# RF_Antenna_Power.net
KiCad netlist of a schematic drawn in Altium Designer
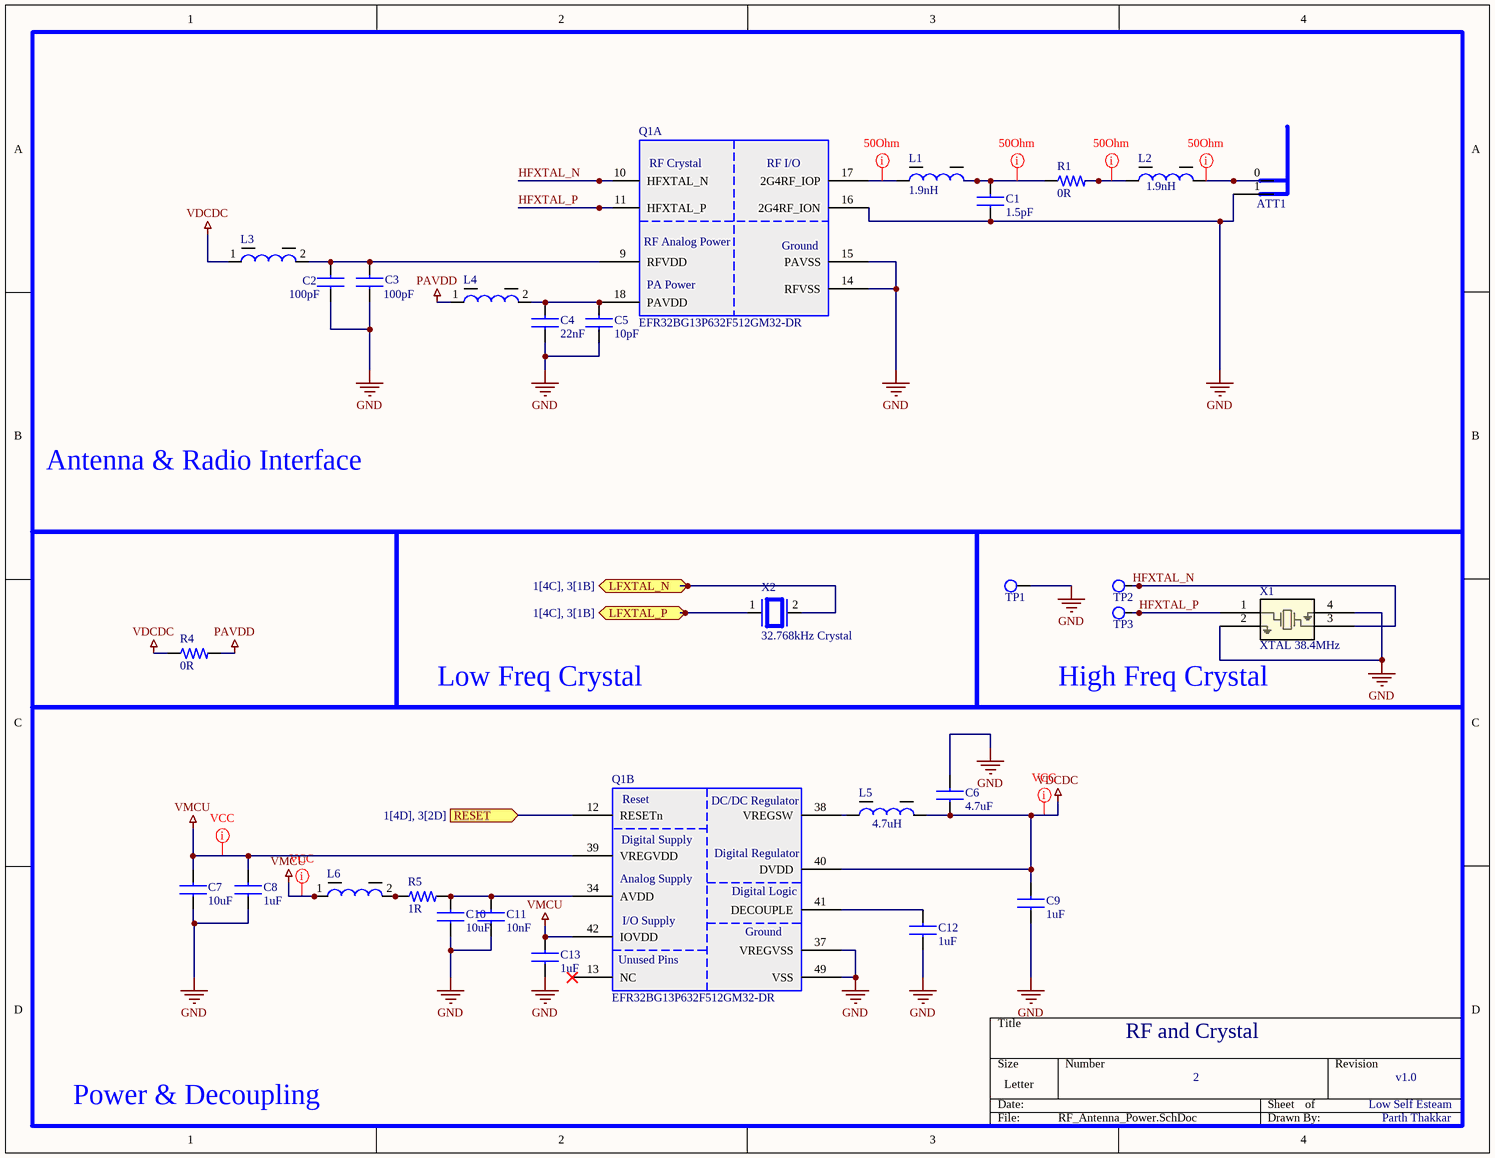
[diagram p0: RF_Antenna_Power.SchDoc]

(export (version "E")
  (design (tool "Eeschema 10.0.6"))
  (components
    (comp (ref "ATT1")
      (value "F_Interverted")
      (footprint "F_Inverted")
      (description "For 50Ohm impedence, Inverted F antenna")
      (libsource (lib "Keyboard_parts") (part "F_Interverted"))
    )
    (comp (ref "C1")
      (value "1.5pF")
      (footprint "Capacitor 0402")
      (fields
        (field (name "MANUFACTURER") "Murata")
        (field (name "MANUFACTURER PART NUMBER") "GJM1555C1H1R5WB01D")
        (field (name "Comment") "CAP 1.5pF 50V 0402")
      )
      (libsource (lib "Keyboard_parts") (part "CAP 1.5pF 50V 0402"))
    )
    (comp (ref "C2")
      (value "100pF")
      (footprint "Capacitor 0603")
      (fields
        (field (name "MANUFACTURER") "Murata")
        (field (name "MANUFACTURER PART NUMBER") "GCM1885C2A101JA16D")
        (field (name "Comment") "CAP 100pF 100V 0603")
      )
      (libsource (lib "Keyboard_parts") (part "CAP 100pF 100V 0603"))
    )
    (comp (ref "C3")
      (value "100pF")
      (footprint "Capacitor 0603")
      (fields
        (field (name "MANUFACTURER") "Murata")
        (field (name "MANUFACTURER PART NUMBER") "GCM1885C2A101JA16D")
        (field (name "Comment") "CAP 100pF 100V 0603")
      )
      (libsource (lib "Keyboard_parts") (part "CAP 100pF 100V 0603"))
    )
    (comp (ref "C4")
      (value "22nF")
      (footprint "Capacitor 0603")
      (fields
        (field (name "MANUFACTURER") "Murata")
        (field (name "MANUFACTURER PART NUMBER") "GRM155R71H223KA12D")
        (field (name "Comment") "CAP 220nF 50V 0603")
      )
      (libsource (lib "Keyboard_parts") (part "CAP 220nF 50V 0603"))
    )
    (comp (ref "C5")
      (value "10pF")
      (footprint "Capacitor 0603")
      (fields
        (field (name "MANUFACTURER") "Murata")
        (field (name "MANUFACTURER PART NUMBER") "GRM1555C1H100FA01D")
        (field (name "Comment") "CAP 10pF 50V 0603")
      )
      (libsource (lib "Keyboard_parts") (part "CAP 10pF 50V 0603"))
    )
    (comp (ref "C6")
      (value "4.7uF")
      (footprint "Capacitor 0603")
      (fields
        (field (name "MANUFACTURER") "Murata")
        (field (name "MANUFACTURER PART NUMBER") "GRT188R61E475KE13D")
        (field (name "Comment") "CAP 4.7uF 25V 0603")
      )
      (libsource (lib "Keyboard_parts") (part "CAP 4.7uF 25V 0603"))
    )
    (comp (ref "C7")
      (value "10uF")
      (footprint "Capacitor 0603")
      (fields
        (field (name "MANUFACTURER") "Murata")
        (field (name "MANUFACTURER PART NUMBER") "GRM188R61A106ME69D")
        (field (name "Comment") "CAP 10uF 10V 0603")
      )
      (libsource (lib "Keyboard_parts") (part "CAP 10uF 10V 0603"))
    )
    (comp (ref "C8")
      (value "1uF")
      (footprint "Capacitor 0603")
      (fields
        (field (name "MANUFACTURER") "Murata")
        (field (name "MANUFACTURER PART NUMBER") "GRM188R61A105KA61D")
        (field (name "Comment") "CAP 1uF 10V 0603")
      )
      (libsource (lib "Keyboard_parts") (part "CAP 1uF 10V 0603"))
    )
    (comp (ref "C9")
      (value "1uF")
      (footprint "Capacitor 0603")
      (fields
        (field (name "MANUFACTURER") "Murata")
        (field (name "MANUFACTURER PART NUMBER") "GRM188R61A105KA61D")
        (field (name "Comment") "CAP 1uF 10V 0603")
      )
      (libsource (lib "Keyboard_parts") (part "CAP 1uF 10V 0603"))
    )
    (comp (ref "C10")
      (value "10uF")
      (footprint "Capacitor 0603")
      (fields
        (field (name "MANUFACTURER") "Murata")
        (field (name "MANUFACTURER PART NUMBER") "GRM188R61A106ME69D")
        (field (name "Comment") "CAP 10uF 10V 0603")
      )
      (libsource (lib "Keyboard_parts") (part "CAP 10uF 10V 0603"))
    )
    (comp (ref "C11")
      (value "10nF")
      (footprint "Capacitor 0603")
      (fields
        (field (name "MANUFACTURER") "Murata")
        (field (name "MANUFACTURER PART NUMBER") "GCM188R72A103KA37D")
        (field (name "Comment") "CAP 10nF 100V 0603")
      )
      (libsource (lib "Keyboard_parts") (part "CAP 10nF 100V 0603"))
    )
    (comp (ref "C12")
      (value "1uF")
      (footprint "Capacitor 0603")
      (fields
        (field (name "MANUFACTURER") "Murata")
        (field (name "MANUFACTURER PART NUMBER") "GRM188R61A105KA61D")
        (field (name "Comment") "CAP 1uF 10V 0603")
      )
      (libsource (lib "Keyboard_parts") (part "CAP 1uF 10V 0603"))
    )
    (comp (ref "C13")
      (value "1uF")
      (footprint "Capacitor 0603")
      (fields
        (field (name "MANUFACTURER") "Murata")
        (field (name "MANUFACTURER PART NUMBER") "GRM188R61A105KA61D")
        (field (name "Comment") "CAP 1uF 10V 0603")
      )
      (libsource (lib "Keyboard_parts") (part "CAP 1uF 10V 0603"))
    )
    (comp (ref "L1")
      (value "1.9nH")
      (footprint "Ferrite 0402")
      (description "Inductor Chip 1.9nH 0.3nH Tolerance 2-Pin 0402 Paper T/R")
      (fields
        (field (name "MANUFACTURER") "Murata")
        (field (name "MANUFACTURER PART NUMBER") "LQG15WZ1N9S02D")
      )
      (libsource (lib "Keyboard_parts") (part "IND 1.9nH 0402"))
    )
    (comp (ref "L2")
      (value "1.9nH")
      (footprint "Ferrite 0402")
      (description "Inductor Chip 1.9nH 0.3nH Tolerance 2-Pin 0402 Paper T/R")
      (fields
        (field (name "MANUFACTURER") "Murata")
        (field (name "MANUFACTURER PART NUMBER") "LQG15WZ1N9S02D")
      )
      (libsource (lib "Keyboard_parts") (part "IND 1.9nH 0402"))
    )
    (comp (ref "L3")
      (value "Ferrite Bead 600(601) 1LN")
      (footprint "Ferrite 0603")
      (description "RFVDD, PAVDD, EFR")
      (fields
        (field (name "MANUFACTURER") "Murata")
        (field (name "MANUFACTURER PART NUMBER") "BLM18AG601SN1D")
      )
      (libsource (lib "Keyboard_parts") (part "Ferrite Bead 600(601) 1LN"))
    )
    (comp (ref "L4")
      (value "Ferrite Bead 600(601) 1LN")
      (footprint "Ferrite 0603")
      (description "RFVDD, PAVDD, EFR")
      (fields
        (field (name "MANUFACTURER") "Murata")
        (field (name "MANUFACTURER PART NUMBER") "BLM18AG601SN1D")
      )
      (libsource (lib "Keyboard_parts") (part "Ferrite Bead 600(601) 1LN"))
    )
    (comp (ref "L5")
      (value "IND 4.7uH 1515")
      (footprint "IND 22uH (1.6x4.3)")
      (description "General Purpose Inductor, 4.7uH, 30%, 1 Element, Ferrite-Core, SMD, 1515")
      (fields
        (field (name "MANUFACTURER") "Wurth Electronics")
        (field (name "MANUFACTURER PART NUMBER") "744031004")
        (field (name "INDUCTANCE-NOM (L)") "4.7uH")
      )
      (libsource (lib "Keyboard_parts") (part "IND 4.7uH 1515"))
    )
    (comp (ref "L6")
      (value "Farrite Bead 102(1k)")
      (footprint "Ferrite 0402")
      (description "Ferrite Chip, 1 Function(s), 0.05A, 2 Pin(s)")
      (fields
        (field (name "MANUFACTURER") "Wurth Electronics")
        (field (name "MANUFACTURER PART NUMBER") "742841210")
      )
      (libsource (lib "Keyboard_parts") (part "Farrite Bead 102(1k)"))
    )
    (comp (ref "Q1")
      (value "EFR32BG13P632F512GM32-DR")
      (footprint "EFR32BG")
      (description "BLue Gecko")
      (fields (field (name "MANUFACTURER") "Silicon Labs"))
      (libsource (lib "Keyboard_parts") (part "EFR32BG13P632F512GM32-DR"))
    )
    (comp (ref "R1")
      (value "0R")
      (footprint "Resistor 0402")
      (description "Metal Glaze/thick Film, 0.0625W, 0ohm, Surface Mount, 0402")
      (fields
        (field (name "MANUFACTURER") "Yageo")
        (field (name "MANUFACTURER PART NUMBER") "RC0402JR-070RL")
      )
      (libsource (lib "Keyboard_parts") (part "RES 0R 0402"))
    )
    (comp (ref "R4")
      (value "0R")
      (footprint "Resistor 0402")
      (description "Metal Glaze/thick Film, 0.0625W, 0ohm, Surface Mount, 0402")
      (fields
        (field (name "MANUFACTURER") "Yageo")
        (field (name "MANUFACTURER PART NUMBER") "RC0402JR-070RL")
      )
      (libsource (lib "Keyboard_parts") (part "RES 0R 0402"))
    )
    (comp (ref "R5")
      (value "1R")
      (footprint "Resistor 0603")
      (fields
        (field (name "MANUFACTURER") "Yageo")
        (field (name "MANUFACTURER PART NUMBER") "RC0603FR-071RL")
        (field (name "TOLERANCE") "1%")
      )
      (libsource (lib "Keyboard_parts") (part "RES 1R 0603"))
    )
    (comp (ref "TP1")
      (value "Test point")
      (footprint "Test Point")
      (libsource (lib "Keyboard_parts") (part "Test point"))
    )
    (comp (ref "TP2")
      (value "Test point")
      (footprint "Test Point")
      (libsource (lib "Keyboard_parts") (part "Test point"))
    )
    (comp (ref "TP3")
      (value "Test point")
      (footprint "Test Point")
      (libsource (lib "Keyboard_parts") (part "Test point"))
    )
    (comp (ref "X1")
      (value "XTAL 38.4MHz")
      (footprint "XTAL 38.4MHz")
      (description "Crystal 38.4000MHZ 10PF SMD")
      (fields
        (field (name "MANUFACTURER") "Murata")
        (field (name "MANUFACTURER PART NUMBER") "XRCGB38M400F1S3JR0")
      )
      (libsource (lib "Keyboard_parts") (part "XTAL 38.4MHz"))
    )
    (comp (ref "X2")
      (value "32.768kHz Crystal")
      (footprint "XTAL_32.768KHZ-T")
      (description "Crystal 0.032768MHz ±20ppm (Tol) 12.5pF Flexural 70000Ohm 2-Pin CSMD T/R")
      (fields
        (field (name "MANUFACTURER") "Abracon")
        (field (name "MANUFACTURER PART NUMBER") "ABS07-32.768KHZ-H-T")
      )
      (libsource (lib "Keyboard_parts") (part "32.768kHz Crystal"))
    )
  )
  (nets
    (net (code "1") (name "/HFXTAL_N") (class "Default")
      (node (ref "Q1") (pin "10") (pinfunction "HFXTAL_N_10") (pintype "passive"))
      (node (ref "TP2") (pin "1") (pinfunction "1_1") (pintype "passive"))
      (node (ref "X1") (pin "3") (pinfunction "3_3") (pintype "passive"))
    )
    (net (code "2") (name "/HFXTAL_P") (class "Default")
      (node (ref "Q1") (pin "11") (pinfunction "HFXTAL_P_11") (pintype "passive"))
      (node (ref "TP3") (pin "1") (pinfunction "1_1") (pintype "passive"))
      (node (ref "X1") (pin "1") (pinfunction "1_1") (pintype "passive"))
    )
    (net (code "3") (name "/LFXTAL_N") (class "Default")
      (node (ref "X2") (pin "2") (pinfunction "2_2") (pintype "passive"))
    )
    (net (code "4") (name "/LFXTAL_P") (class "Default")
      (node (ref "X2") (pin "1") (pinfunction "1_1") (pintype "passive"))
    )
    (net (code "5") (name "/RESET") (class "Default")
      (node (ref "Q1") (pin "12") (pinfunction "RESETn_12") (pintype "passive"))
    )
    (net (code "6") (name "GND") (class "Default")
      (node (ref "ATT1") (pin "1") (pinfunction "GND_1") (pintype "passive"))
      (node (ref "C1") (pin "2") (pinfunction "2_2") (pintype "passive"))
      (node (ref "C10") (pin "2") (pinfunction "2_2") (pintype "passive"))
      (node (ref "C11") (pin "2") (pinfunction "2_2") (pintype "passive"))
      (node (ref "C12") (pin "2") (pinfunction "2_2") (pintype "passive"))
      (node (ref "C13") (pin "2") (pinfunction "2_2") (pintype "passive"))
      (node (ref "C2") (pin "2") (pinfunction "2_2") (pintype "passive"))
      (node (ref "C3") (pin "2") (pinfunction "2_2") (pintype "passive"))
      (node (ref "C4") (pin "2") (pinfunction "2_2") (pintype "passive"))
      (node (ref "C5") (pin "2") (pinfunction "2_2") (pintype "passive"))
      (node (ref "C6") (pin "2") (pinfunction "2_2") (pintype "passive"))
      (node (ref "C7") (pin "2") (pinfunction "2_2") (pintype "passive"))
      (node (ref "C8") (pin "2") (pinfunction "2_2") (pintype "passive"))
      (node (ref "C9") (pin "2") (pinfunction "2_2") (pintype "passive"))
      (node (ref "Q1") (pin "14") (pinfunction "RFVSS_14") (pintype "power_in"))
      (node (ref "Q1") (pin "15") (pinfunction "PAVSS_15") (pintype "power_in"))
      (node (ref "Q1") (pin "16") (pinfunction "2G4RF_ION_16") (pintype "passive"))
      (node (ref "Q1") (pin "37") (pinfunction "VREGVSS_37") (pintype "power_in"))
      (node (ref "Q1") (pin "49") (pinfunction "VSS_49") (pintype "power_in"))
      (node (ref "TP1") (pin "1") (pinfunction "1_1") (pintype "passive"))
      (node (ref "X1") (pin "2") (pinfunction "2_2") (pintype "passive"))
      (node (ref "X1") (pin "4") (pinfunction "4_4") (pintype "passive"))
    )
    (net (code "7") (name "Net-(ATT1-FEED)") (class "Default")
      (node (ref "ATT1") (pin "0") (pinfunction "FEED_0") (pintype "passive"))
      (node (ref "L2") (pin "2") (pinfunction "2_2") (pintype "passive"))
    )
    (net (code "8") (name "Net-(C1-Pad1)") (class "Default")
      (node (ref "C1") (pin "1") (pinfunction "1_1") (pintype "passive"))
      (node (ref "L1") (pin "2") (pinfunction "2_2") (pintype "passive"))
      (node (ref "R1") (pin "1") (pinfunction "1_1") (pintype "passive"))
    )
    (net (code "9") (name "Net-(L2-Pad1)") (class "Default")
      (node (ref "L2") (pin "1") (pinfunction "1_1") (pintype "passive"))
      (node (ref "R1") (pin "2") (pinfunction "2_2") (pintype "passive"))
    )
    (net (code "10") (name "Net-(L6-Pad2)") (class "Default")
      (node (ref "L6") (pin "2") (pinfunction "2_2") (pintype "passive"))
      (node (ref "R5") (pin "1") (pinfunction "1_1") (pintype "passive"))
    )
    (net (code "11") (name "Net-(Q1A-2G4RF_IOP)") (class "Default")
      (node (ref "L1") (pin "1") (pinfunction "1_1") (pintype "passive"))
      (node (ref "Q1") (pin "17") (pinfunction "2G4RF_IOP_17") (pintype "passive"))
    )
    (net (code "12") (name "Net-(Q1A-PAVDD)") (class "Default")
      (node (ref "C4") (pin "1") (pinfunction "1_1") (pintype "passive"))
      (node (ref "C5") (pin "1") (pinfunction "1_1") (pintype "passive"))
      (node (ref "L4") (pin "2") (pinfunction "2_2") (pintype "passive"))
      (node (ref "Q1") (pin "18") (pinfunction "PAVDD_18") (pintype "power_in"))
    )
    (net (code "13") (name "Net-(Q1A-RFVDD)") (class "Default")
      (node (ref "C2") (pin "1") (pinfunction "1_1") (pintype "passive"))
      (node (ref "C3") (pin "1") (pinfunction "1_1") (pintype "passive"))
      (node (ref "L3") (pin "2") (pinfunction "2_2") (pintype "passive"))
      (node (ref "Q1") (pin "9") (pinfunction "RFVDD_9") (pintype "power_in"))
    )
    (net (code "14") (name "Net-(Q1B-AVDD)") (class "Default")
      (node (ref "C10") (pin "1") (pinfunction "1_1") (pintype "passive"))
      (node (ref "C11") (pin "1") (pinfunction "1_1") (pintype "passive"))
      (node (ref "Q1") (pin "34") (pinfunction "AVDD_34") (pintype "power_in"))
      (node (ref "R5") (pin "2") (pinfunction "2_2") (pintype "passive"))
    )
    (net (code "15") (name "Net-(Q1B-DECOUPLE)") (class "Default")
      (node (ref "C12") (pin "1") (pinfunction "1_1") (pintype "passive"))
      (node (ref "Q1") (pin "41") (pinfunction "DECOUPLE_41") (pintype "passive"))
    )
    (net (code "16") (name "Net-(Q1B-VREGSW)") (class "Default")
      (node (ref "L5") (pin "1") (pinfunction "1_1") (pintype "passive"))
      (node (ref "Q1") (pin "38") (pinfunction "VREGSW_38") (pintype "power_in"))
    )
    (net (code "17") (name "PAVDD") (class "Default")
      (node (ref "L4") (pin "1") (pinfunction "1_1") (pintype "passive"))
      (node (ref "R4") (pin "2") (pinfunction "2_2") (pintype "passive"))
    )
    (net (code "18") (name "VDCDC") (class "Default")
      (node (ref "C6") (pin "1") (pinfunction "1_1") (pintype "passive"))
      (node (ref "C9") (pin "1") (pinfunction "1_1") (pintype "passive"))
      (node (ref "L3") (pin "1") (pinfunction "1_1") (pintype "passive"))
      (node (ref "L5") (pin "2") (pinfunction "2_2") (pintype "passive"))
      (node (ref "Q1") (pin "40") (pinfunction "DVDD_40") (pintype "power_in"))
      (node (ref "R4") (pin "1") (pinfunction "1_1") (pintype "passive"))
    )
    (net (code "19") (name "VMCU") (class "Default")
      (node (ref "C13") (pin "1") (pinfunction "1_1") (pintype "passive"))
      (node (ref "C7") (pin "1") (pinfunction "1_1") (pintype "passive"))
      (node (ref "C8") (pin "1") (pinfunction "1_1") (pintype "passive"))
      (node (ref "L6") (pin "1") (pinfunction "1_1") (pintype "passive"))
      (node (ref "Q1") (pin "39") (pinfunction "VREGVDD_39") (pintype "power_in"))
      (node (ref "Q1") (pin "42") (pinfunction "IOVDD_42") (pintype "power_in"))
    )
    (net (code "20") (name "unconnected-(Q1B-NC-Pad13)") (class "Default")
      (node (ref "Q1") (pin "13") (pinfunction "NC_13") (pintype "passive+no_connect"))
    )
  )
)
